# DMG_Control_Panel.net
KiCad netlist of a schematic drawn in EAGLE
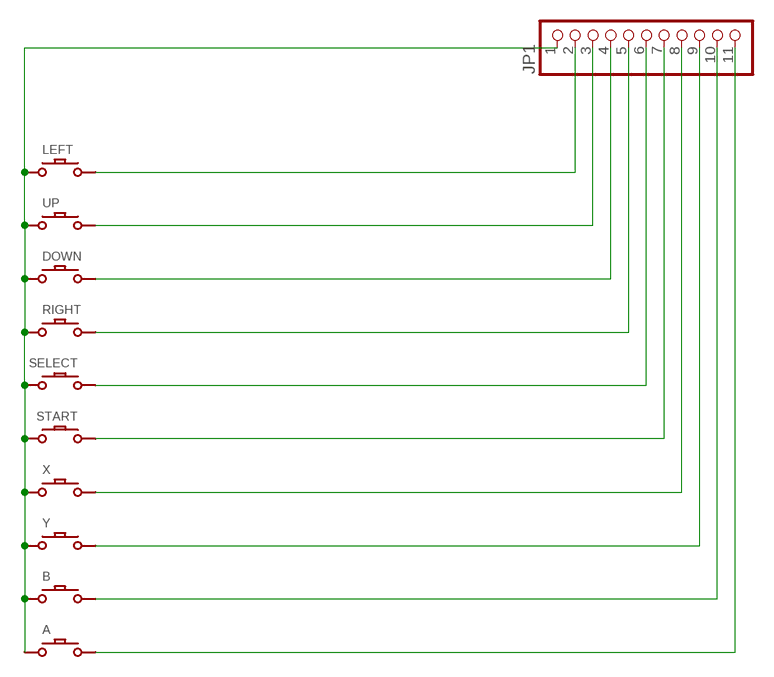
[diagram p0: schematic, sheet 1]

(export (version "E")
  (design (tool "Eeschema 10.0.6"))
  (components
    (comp (ref "A")
      (value "DMG-BTN")
      (footprint "eagle-import:DMG-BTN")
      (libsource (lib "eagle-import") (part "DMG-BTNREGULAR"))
    )
    (comp (ref "B")
      (value "DMG-BTN")
      (footprint "eagle-import:DMG-BTN")
      (libsource (lib "eagle-import") (part "DMG-BTNREGULAR"))
    )
    (comp (ref "DOWN")
      (value "DMG-BTN")
      (footprint "eagle-import:DMG-BTN")
      (libsource (lib "eagle-import") (part "DMG-BTNREGULAR"))
    )
    (comp (ref "JP1")
      (value "PINHD-1X11M")
      (footprint "eagle-import:1X11M")
      (libsource (lib "eagle-import") (part "PINHD-1X11M"))
    )
    (comp (ref "LEFT")
      (value "DMG-BTN")
      (footprint "eagle-import:DMG-BTN")
      (libsource (lib "eagle-import") (part "DMG-BTNREGULAR"))
    )
    (comp (ref "RIGHT")
      (value "DMG-BTN")
      (footprint "eagle-import:DMG-BTN")
      (libsource (lib "eagle-import") (part "DMG-BTNREGULAR"))
    )
    (comp (ref "SELECT")
      (value "DMG-BTN")
      (footprint "eagle-import:DMG-SEL")
      (libsource (lib "eagle-import") (part "DMG-BTNSELECT"))
    )
    (comp (ref "START")
      (value "DMG-BTN")
      (footprint "eagle-import:DMG-SEL")
      (libsource (lib "eagle-import") (part "DMG-BTNSELECT"))
    )
    (comp (ref "UP")
      (value "DMG-BTN")
      (footprint "eagle-import:DMG-BTN")
      (libsource (lib "eagle-import") (part "DMG-BTNREGULAR"))
    )
    (comp (ref "X")
      (value "DMG-BTN")
      (footprint "eagle-import:DMG-BTN")
      (libsource (lib "eagle-import") (part "DMG-BTNREGULAR"))
    )
    (comp (ref "Y")
      (value "DMG-BTN")
      (footprint "eagle-import:DMG-BTN")
      (libsource (lib "eagle-import") (part "DMG-BTNREGULAR"))
    )
  )
  (nets
    (net (code "1") (name "Net-(A-PadP$1)") (class "Default")
      (node (ref "A") (pin "P$1") (pinfunction "P$1_P$1") (pintype "bidirectional"))
      (node (ref "B") (pin "P$1") (pinfunction "P$1_P$1") (pintype "bidirectional"))
      (node (ref "DOWN") (pin "P$1") (pinfunction "P$1_P$1") (pintype "bidirectional"))
      (node (ref "JP1") (pin "1") (pinfunction "1_1") (pintype "passive"))
      (node (ref "LEFT") (pin "P$1") (pinfunction "P$1_P$1") (pintype "bidirectional"))
      (node (ref "RIGHT") (pin "P$1") (pinfunction "P$1_P$1") (pintype "bidirectional"))
      (node (ref "SELECT") (pin "P$2") (pinfunction "P$2_P$2") (pintype "bidirectional"))
      (node (ref "START") (pin "P$2") (pinfunction "P$2_P$2") (pintype "bidirectional"))
      (node (ref "UP") (pin "P$1") (pinfunction "P$1_P$1") (pintype "bidirectional"))
      (node (ref "X") (pin "P$1") (pinfunction "P$1_P$1") (pintype "bidirectional"))
      (node (ref "Y") (pin "P$1") (pinfunction "P$1_P$1") (pintype "bidirectional"))
    )
    (net (code "2") (name "Net-(A-PadP$2)") (class "Default")
      (node (ref "A") (pin "P$2") (pinfunction "P$2_P$2") (pintype "bidirectional"))
      (node (ref "JP1") (pin "11") (pinfunction "11_11") (pintype "passive"))
    )
    (net (code "3") (name "Net-(B-PadP$2)") (class "Default")
      (node (ref "B") (pin "P$2") (pinfunction "P$2_P$2") (pintype "bidirectional"))
      (node (ref "JP1") (pin "10") (pinfunction "10_10") (pintype "passive"))
    )
    (net (code "4") (name "Net-(DOWN-PadP$2)") (class "Default")
      (node (ref "DOWN") (pin "P$2") (pinfunction "P$2_P$2") (pintype "bidirectional"))
      (node (ref "JP1") (pin "4") (pinfunction "4_4") (pintype "passive"))
    )
    (net (code "5") (name "Net-(JP1-Pad2)") (class "Default")
      (node (ref "JP1") (pin "2") (pinfunction "2_2") (pintype "passive"))
      (node (ref "LEFT") (pin "P$2") (pinfunction "P$2_P$2") (pintype "bidirectional"))
    )
    (net (code "6") (name "Net-(JP1-Pad3)") (class "Default")
      (node (ref "JP1") (pin "3") (pinfunction "3_3") (pintype "passive"))
      (node (ref "UP") (pin "P$2") (pinfunction "P$2_P$2") (pintype "bidirectional"))
    )
    (net (code "7") (name "Net-(JP1-Pad5)") (class "Default")
      (node (ref "JP1") (pin "5") (pinfunction "5_5") (pintype "passive"))
      (node (ref "RIGHT") (pin "P$2") (pinfunction "P$2_P$2") (pintype "bidirectional"))
    )
    (net (code "8") (name "Net-(JP1-Pad6)") (class "Default")
      (node (ref "JP1") (pin "6") (pinfunction "6_6") (pintype "passive"))
      (node (ref "SELECT") (pin "P$1") (pinfunction "P$1_P$1") (pintype "bidirectional"))
    )
    (net (code "9") (name "Net-(JP1-Pad7)") (class "Default")
      (node (ref "JP1") (pin "7") (pinfunction "7_7") (pintype "passive"))
      (node (ref "START") (pin "P$1") (pinfunction "P$1_P$1") (pintype "bidirectional"))
    )
    (net (code "10") (name "Net-(JP1-Pad8)") (class "Default")
      (node (ref "JP1") (pin "8") (pinfunction "8_8") (pintype "passive"))
      (node (ref "X") (pin "P$2") (pinfunction "P$2_P$2") (pintype "bidirectional"))
    )
    (net (code "11") (name "Net-(JP1-Pad9)") (class "Default")
      (node (ref "JP1") (pin "9") (pinfunction "9_9") (pintype "passive"))
      (node (ref "Y") (pin "P$2") (pinfunction "P$2_P$2") (pintype "bidirectional"))
    )
  )
)
